# 7seg.net
KiCad netlist of a schematic drawn in EAGLE
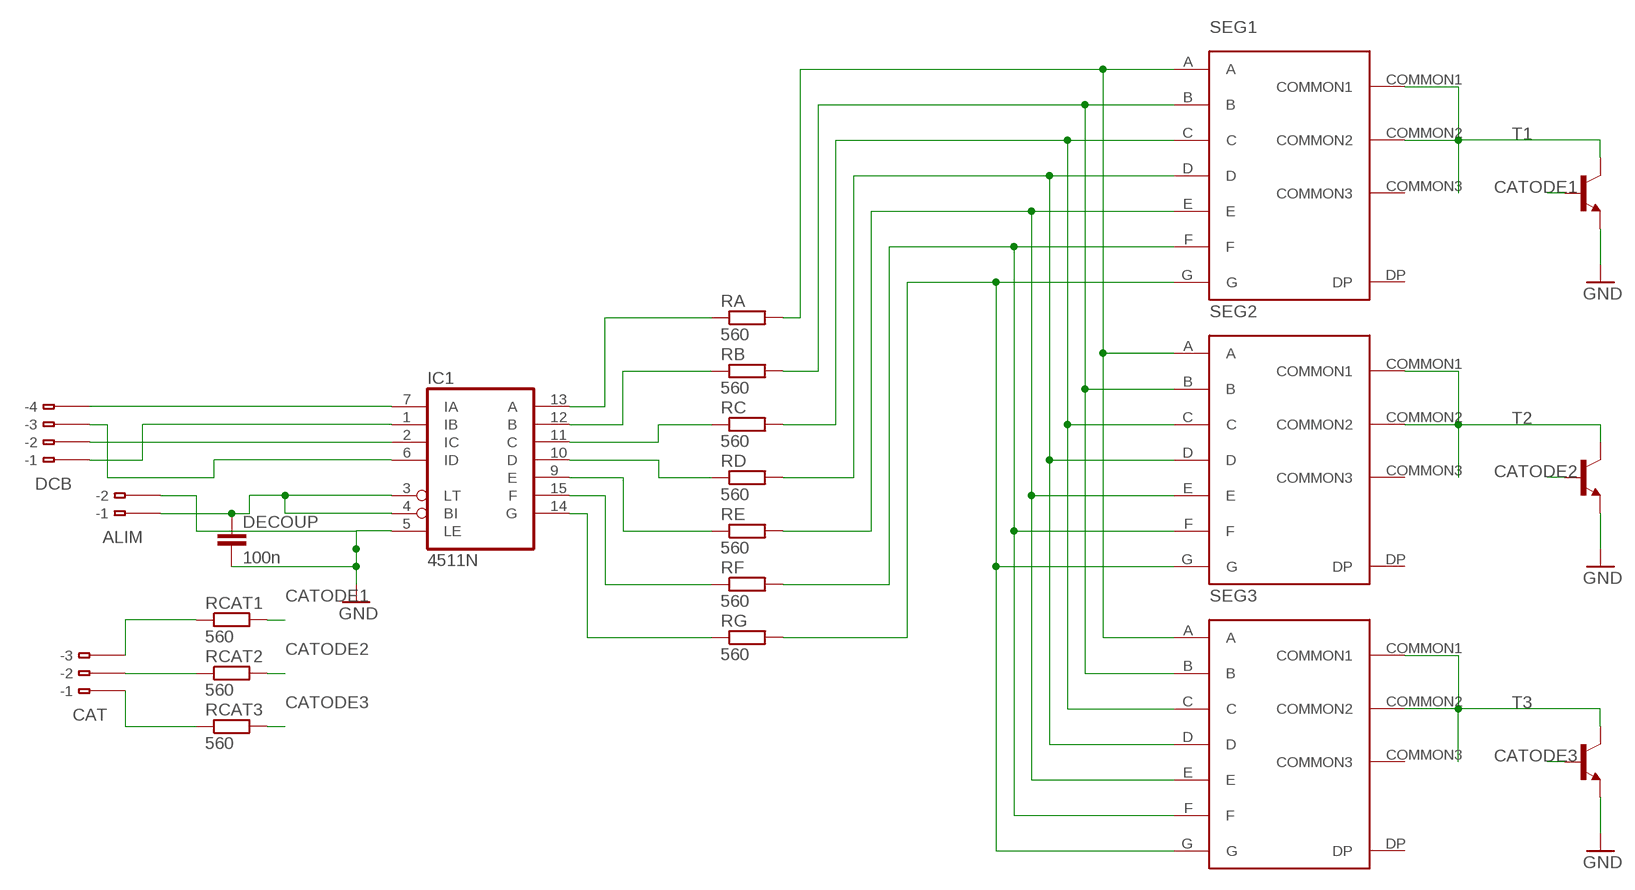
[diagram p0: schematic, sheet 1]

(export (version "E")
  (design (tool "Eeschema 10.0.6"))
  (components
    (comp (ref "ALIM")
      (value "233-102")
      (footprint "eagle-import:233-102")
      (libsource (lib "eagle-import") (part "233-102"))
    )
    (comp (ref "CAT")
      (value "233-103")
      (footprint "eagle-import:233-103")
      (libsource (lib "eagle-import") (part "233-103"))
    )
    (comp (ref "DCB")
      (value "233-104")
      (footprint "eagle-import:233-104")
      (libsource (lib "eagle-import") (part "233-104"))
    )
    (comp (ref "DECOUP")
      (value "100n")
      (footprint "eagle-import:C2012")
      (libsource (lib "eagle-import") (part "C-EUC2012"))
    )
    (comp (ref "IC1")
      (value "4511N")
      (footprint "eagle-import:DIL16")
      (libsource (lib "eagle-import") (part "4511N"))
    )
    (comp (ref "RA")
      (value "560")
      (footprint "eagle-import:M2012")
      (libsource (lib "eagle-import") (part "R-EU_M2012"))
    )
    (comp (ref "RB")
      (value "560")
      (footprint "eagle-import:M2012")
      (libsource (lib "eagle-import") (part "R-EU_M2012"))
    )
    (comp (ref "RC")
      (value "560")
      (footprint "eagle-import:M2012")
      (libsource (lib "eagle-import") (part "R-EU_M2012"))
    )
    (comp (ref "RCAT1")
      (value "560")
      (footprint "eagle-import:M2012")
      (libsource (lib "eagle-import") (part "R-EU_M2012"))
    )
    (comp (ref "RCAT2")
      (value "560")
      (footprint "eagle-import:M2012")
      (libsource (lib "eagle-import") (part "R-EU_M2012"))
    )
    (comp (ref "RCAT3")
      (value "560")
      (footprint "eagle-import:M2012")
      (libsource (lib "eagle-import") (part "R-EU_M2012"))
    )
    (comp (ref "RD")
      (value "560")
      (footprint "eagle-import:M2012")
      (libsource (lib "eagle-import") (part "R-EU_M2012"))
    )
    (comp (ref "RE")
      (value "560")
      (footprint "eagle-import:M2012")
      (libsource (lib "eagle-import") (part "R-EU_M2012"))
    )
    (comp (ref "RF")
      (value "560")
      (footprint "eagle-import:M2012")
      (libsource (lib "eagle-import") (part "R-EU_M2012"))
    )
    (comp (ref "RG")
      (value "560")
      (footprint "eagle-import:M2012")
      (libsource (lib "eagle-import") (part "R-EU_M2012"))
    )
    (comp (ref "SEG1")
      (value "7SEG_33MMMARK1")
      (footprint "eagle-import:7SEG_33MM")
      (libsource (lib "eagle-import") (part "7SEG_33MMMARK1"))
    )
    (comp (ref "SEG2")
      (value "7SEG_33MMMARK1")
      (footprint "eagle-import:7SEG_33MM")
      (libsource (lib "eagle-import") (part "7SEG_33MMMARK1"))
    )
    (comp (ref "SEG3")
      (value "7SEG_33MMMARK1")
      (footprint "eagle-import:7SEG_33MM")
      (libsource (lib "eagle-import") (part "7SEG_33MMMARK1"))
    )
    (comp (ref "T1")
      (value "BF844-NPN-TO92-CBE")
      (footprint "eagle-import:TO92-CBE")
      (libsource (lib "eagle-import") (part "-NPN-TO92-CBEBF844"))
    )
    (comp (ref "T2")
      (value "BF844-NPN-TO92-CBE")
      (footprint "eagle-import:TO92-CBE")
      (libsource (lib "eagle-import") (part "-NPN-TO92-CBEBF844"))
    )
    (comp (ref "T3")
      (value "BF844-NPN-TO92-CBE")
      (footprint "eagle-import:TO92-CBE")
      (libsource (lib "eagle-import") (part "-NPN-TO92-CBEBF844"))
    )
  )
  (nets
    (net (code "1") (name "/CATODE1") (class "Default")
      (node (ref "RCAT1") (pin "2") (pinfunction "2_2") (pintype "passive"))
      (node (ref "T1") (pin "B") (pinfunction "B_B") (pintype "passive"))
    )
    (net (code "2") (name "/CATODE2") (class "Default")
      (node (ref "RCAT2") (pin "2") (pinfunction "2_2") (pintype "passive"))
      (node (ref "T2") (pin "B") (pinfunction "B_B") (pintype "passive"))
    )
    (net (code "3") (name "/CATODE3") (class "Default")
      (node (ref "RCAT3") (pin "2") (pinfunction "2_2") (pintype "passive"))
      (node (ref "T3") (pin "B") (pinfunction "B_B") (pintype "passive"))
    )
    (net (code "4") (name "GND") (class "Default")
      (node (ref "ALIM") (pin "B2") (pinfunction "B-2_B2") (pintype "passive"))
      (node (ref "DECOUP") (pin "2") (pinfunction "2_2") (pintype "passive"))
      (node (ref "IC1") (pin "5") (pinfunction "LE_5") (pintype "input"))
      (node (ref "T1") (pin "E") (pinfunction "E_E") (pintype "passive"))
      (node (ref "T2") (pin "E") (pinfunction "E_E") (pintype "passive"))
      (node (ref "T3") (pin "E") (pinfunction "E_E") (pintype "passive"))
    )
    (net (code "5") (name "Net-(ALIM-B-1)") (class "Default")
      (node (ref "ALIM") (pin "B1") (pinfunction "B-1_B1") (pintype "passive"))
      (node (ref "DECOUP") (pin "1") (pinfunction "1_1") (pintype "passive"))
      (node (ref "IC1") (pin "3") (pinfunction "LT_3") (pintype "input"))
      (node (ref "IC1") (pin "4") (pinfunction "BI_4") (pintype "input"))
    )
    (net (code "6") (name "Net-(CAT-B-1)") (class "Default")
      (node (ref "CAT") (pin "B1") (pinfunction "B-1_B1") (pintype "passive"))
      (node (ref "RCAT3") (pin "1") (pinfunction "1_1") (pintype "passive"))
    )
    (net (code "7") (name "Net-(CAT-B-2)") (class "Default")
      (node (ref "CAT") (pin "B2") (pinfunction "B-2_B2") (pintype "passive"))
      (node (ref "RCAT2") (pin "1") (pinfunction "1_1") (pintype "passive"))
    )
    (net (code "8") (name "Net-(CAT-B-3)") (class "Default")
      (node (ref "CAT") (pin "B3") (pinfunction "B-3_B3") (pintype "passive"))
      (node (ref "RCAT1") (pin "1") (pinfunction "1_1") (pintype "passive"))
    )
    (net (code "9") (name "Net-(DCB-B-1)") (class "Default")
      (node (ref "DCB") (pin "B1") (pinfunction "B-1_B1") (pintype "passive"))
      (node (ref "IC1") (pin "1") (pinfunction "IB_1") (pintype "input"))
    )
    (net (code "10") (name "Net-(DCB-B-2)") (class "Default")
      (node (ref "DCB") (pin "B2") (pinfunction "B-2_B2") (pintype "passive"))
      (node (ref "IC1") (pin "2") (pinfunction "IC_2") (pintype "input"))
    )
    (net (code "11") (name "Net-(DCB-B-3)") (class "Default")
      (node (ref "DCB") (pin "B3") (pinfunction "B-3_B3") (pintype "passive"))
      (node (ref "IC1") (pin "6") (pinfunction "ID_6") (pintype "input"))
    )
    (net (code "12") (name "Net-(DCB-B-4)") (class "Default")
      (node (ref "DCB") (pin "B4") (pinfunction "B-4_B4") (pintype "passive"))
      (node (ref "IC1") (pin "7") (pinfunction "IA_7") (pintype "input"))
    )
    (net (code "13") (name "Net-(IC1A-A)") (class "Default")
      (node (ref "IC1") (pin "13") (pinfunction "A_13") (pintype "output"))
      (node (ref "RA") (pin "1") (pinfunction "1_1") (pintype "passive"))
    )
    (net (code "14") (name "Net-(IC1A-B)") (class "Default")
      (node (ref "IC1") (pin "12") (pinfunction "B_12") (pintype "output"))
      (node (ref "RB") (pin "1") (pinfunction "1_1") (pintype "passive"))
    )
    (net (code "15") (name "Net-(IC1A-C)") (class "Default")
      (node (ref "IC1") (pin "11") (pinfunction "C_11") (pintype "output"))
      (node (ref "RC") (pin "1") (pinfunction "1_1") (pintype "passive"))
    )
    (net (code "16") (name "Net-(IC1A-D)") (class "Default")
      (node (ref "IC1") (pin "10") (pinfunction "D_10") (pintype "output"))
      (node (ref "RD") (pin "1") (pinfunction "1_1") (pintype "passive"))
    )
    (net (code "17") (name "Net-(IC1A-E)") (class "Default")
      (node (ref "IC1") (pin "9") (pinfunction "E_9") (pintype "output"))
      (node (ref "RE") (pin "1") (pinfunction "1_1") (pintype "passive"))
    )
    (net (code "18") (name "Net-(IC1A-F)") (class "Default")
      (node (ref "IC1") (pin "15") (pinfunction "F_15") (pintype "output"))
      (node (ref "RF") (pin "1") (pinfunction "1_1") (pintype "passive"))
    )
    (net (code "19") (name "Net-(IC1A-G)") (class "Default")
      (node (ref "IC1") (pin "14") (pinfunction "G_14") (pintype "output"))
      (node (ref "RG") (pin "1") (pinfunction "1_1") (pintype "passive"))
    )
    (net (code "20") (name "Net-(RA-Pad2)") (class "Default")
      (node (ref "RA") (pin "2") (pinfunction "2_2") (pintype "passive"))
      (node (ref "SEG1") (pin "A") (pinfunction "A_A") (pintype "bidirectional"))
      (node (ref "SEG2") (pin "A") (pinfunction "A_A") (pintype "bidirectional"))
      (node (ref "SEG3") (pin "A") (pinfunction "A_A") (pintype "bidirectional"))
    )
    (net (code "21") (name "Net-(RB-Pad2)") (class "Default")
      (node (ref "RB") (pin "2") (pinfunction "2_2") (pintype "passive"))
      (node (ref "SEG1") (pin "B") (pinfunction "B_B") (pintype "bidirectional"))
      (node (ref "SEG2") (pin "B") (pinfunction "B_B") (pintype "bidirectional"))
      (node (ref "SEG3") (pin "B") (pinfunction "B_B") (pintype "bidirectional"))
    )
    (net (code "22") (name "Net-(RC-Pad2)") (class "Default")
      (node (ref "RC") (pin "2") (pinfunction "2_2") (pintype "passive"))
      (node (ref "SEG1") (pin "C") (pinfunction "C_C") (pintype "bidirectional"))
      (node (ref "SEG2") (pin "C") (pinfunction "C_C") (pintype "bidirectional"))
      (node (ref "SEG3") (pin "C") (pinfunction "C_C") (pintype "bidirectional"))
    )
    (net (code "23") (name "Net-(RD-Pad2)") (class "Default")
      (node (ref "RD") (pin "2") (pinfunction "2_2") (pintype "passive"))
      (node (ref "SEG1") (pin "D") (pinfunction "D_D") (pintype "bidirectional"))
      (node (ref "SEG2") (pin "D") (pinfunction "D_D") (pintype "bidirectional"))
      (node (ref "SEG3") (pin "D") (pinfunction "D_D") (pintype "bidirectional"))
    )
    (net (code "24") (name "Net-(RE-Pad2)") (class "Default")
      (node (ref "RE") (pin "2") (pinfunction "2_2") (pintype "passive"))
      (node (ref "SEG1") (pin "E") (pinfunction "E_E") (pintype "bidirectional"))
      (node (ref "SEG2") (pin "E") (pinfunction "E_E") (pintype "bidirectional"))
      (node (ref "SEG3") (pin "E") (pinfunction "E_E") (pintype "bidirectional"))
    )
    (net (code "25") (name "Net-(RF-Pad2)") (class "Default")
      (node (ref "RF") (pin "2") (pinfunction "2_2") (pintype "passive"))
      (node (ref "SEG1") (pin "F") (pinfunction "F_F") (pintype "bidirectional"))
      (node (ref "SEG2") (pin "F") (pinfunction "F_F") (pintype "bidirectional"))
      (node (ref "SEG3") (pin "F") (pinfunction "F_F") (pintype "bidirectional"))
    )
    (net (code "26") (name "Net-(RG-Pad2)") (class "Default")
      (node (ref "RG") (pin "2") (pinfunction "2_2") (pintype "passive"))
      (node (ref "SEG1") (pin "G") (pinfunction "G_G") (pintype "bidirectional"))
      (node (ref "SEG2") (pin "G") (pinfunction "G_G") (pintype "bidirectional"))
      (node (ref "SEG3") (pin "G") (pinfunction "G_G") (pintype "bidirectional"))
    )
    (net (code "27") (name "Net-(SEG1-PadCOMMON1)") (class "Default")
      (node (ref "SEG1") (pin "COMMON1") (pinfunction "COMMON1_COMMON1") (pintype "bidirectional"))
      (node (ref "SEG1") (pin "COMMON2") (pinfunction "COMMON2_COMMON2") (pintype "bidirectional"))
      (node (ref "T1") (pin "C") (pinfunction "C_C") (pintype "passive"))
    )
    (net (code "28") (name "Net-(SEG2-PadCOMMON1)") (class "Default")
      (node (ref "SEG2") (pin "COMMON1") (pinfunction "COMMON1_COMMON1") (pintype "bidirectional"))
      (node (ref "SEG2") (pin "COMMON2") (pinfunction "COMMON2_COMMON2") (pintype "bidirectional"))
      (node (ref "T2") (pin "C") (pinfunction "C_C") (pintype "passive"))
    )
    (net (code "29") (name "Net-(SEG3-PadCOMMON1)") (class "Default")
      (node (ref "SEG3") (pin "COMMON1") (pinfunction "COMMON1_COMMON1") (pintype "bidirectional"))
      (node (ref "SEG3") (pin "COMMON2") (pinfunction "COMMON2_COMMON2") (pintype "bidirectional"))
      (node (ref "T3") (pin "C") (pinfunction "C_C") (pintype "passive"))
    )
    (net (code "30") (name "unconnected-(ALIM--1-PadA1)") (class "Default")
      (node (ref "ALIM") (pin "A1") (pinfunction "-1_A1") (pintype "passive"))
    )
    (net (code "31") (name "unconnected-(ALIM--2-PadA2)") (class "Default")
      (node (ref "ALIM") (pin "A2") (pinfunction "-2_A2") (pintype "passive"))
    )
    (net (code "32") (name "unconnected-(CAT--1-PadA1)") (class "Default")
      (node (ref "CAT") (pin "A1") (pinfunction "-1_A1") (pintype "passive"))
    )
    (net (code "33") (name "unconnected-(CAT--2-PadA2)") (class "Default")
      (node (ref "CAT") (pin "A2") (pinfunction "-2_A2") (pintype "passive"))
    )
    (net (code "34") (name "unconnected-(CAT--3-PadA3)") (class "Default")
      (node (ref "CAT") (pin "A3") (pinfunction "-3_A3") (pintype "passive"))
    )
    (net (code "35") (name "unconnected-(DCB--1-PadA1)") (class "Default")
      (node (ref "DCB") (pin "A1") (pinfunction "-1_A1") (pintype "passive"))
    )
    (net (code "36") (name "unconnected-(DCB--2-PadA2)") (class "Default")
      (node (ref "DCB") (pin "A2") (pinfunction "-2_A2") (pintype "passive"))
    )
    (net (code "37") (name "unconnected-(DCB--3-PadA3)") (class "Default")
      (node (ref "DCB") (pin "A3") (pinfunction "-3_A3") (pintype "passive"))
    )
    (net (code "38") (name "unconnected-(DCB--4-PadA4)") (class "Default")
      (node (ref "DCB") (pin "A4") (pinfunction "-4_A4") (pintype "passive"))
    )
    (net (code "39") (name "unconnected-(SEG1-PadCOMMON3)") (class "Default")
      (node (ref "SEG1") (pin "COMMON3") (pinfunction "COMMON3_COMMON3") (pintype "bidirectional"))
    )
    (net (code "40") (name "unconnected-(SEG1-PadDP)") (class "Default")
      (node (ref "SEG1") (pin "DP") (pinfunction "DP_DP") (pintype "bidirectional"))
    )
    (net (code "41") (name "unconnected-(SEG2-PadCOMMON3)") (class "Default")
      (node (ref "SEG2") (pin "COMMON3") (pinfunction "COMMON3_COMMON3") (pintype "bidirectional"))
    )
    (net (code "42") (name "unconnected-(SEG2-PadDP)") (class "Default")
      (node (ref "SEG2") (pin "DP") (pinfunction "DP_DP") (pintype "bidirectional"))
    )
    (net (code "43") (name "unconnected-(SEG3-PadCOMMON3)") (class "Default")
      (node (ref "SEG3") (pin "COMMON3") (pinfunction "COMMON3_COMMON3") (pintype "bidirectional"))
    )
    (net (code "44") (name "unconnected-(SEG3-PadDP)") (class "Default")
      (node (ref "SEG3") (pin "DP") (pinfunction "DP_DP") (pintype "bidirectional"))
    )
  )
)
